# pCog102_Wifi_PSPJoy_BLED_TFT.net
KiCad netlist of a schematic drawn in EAGLE
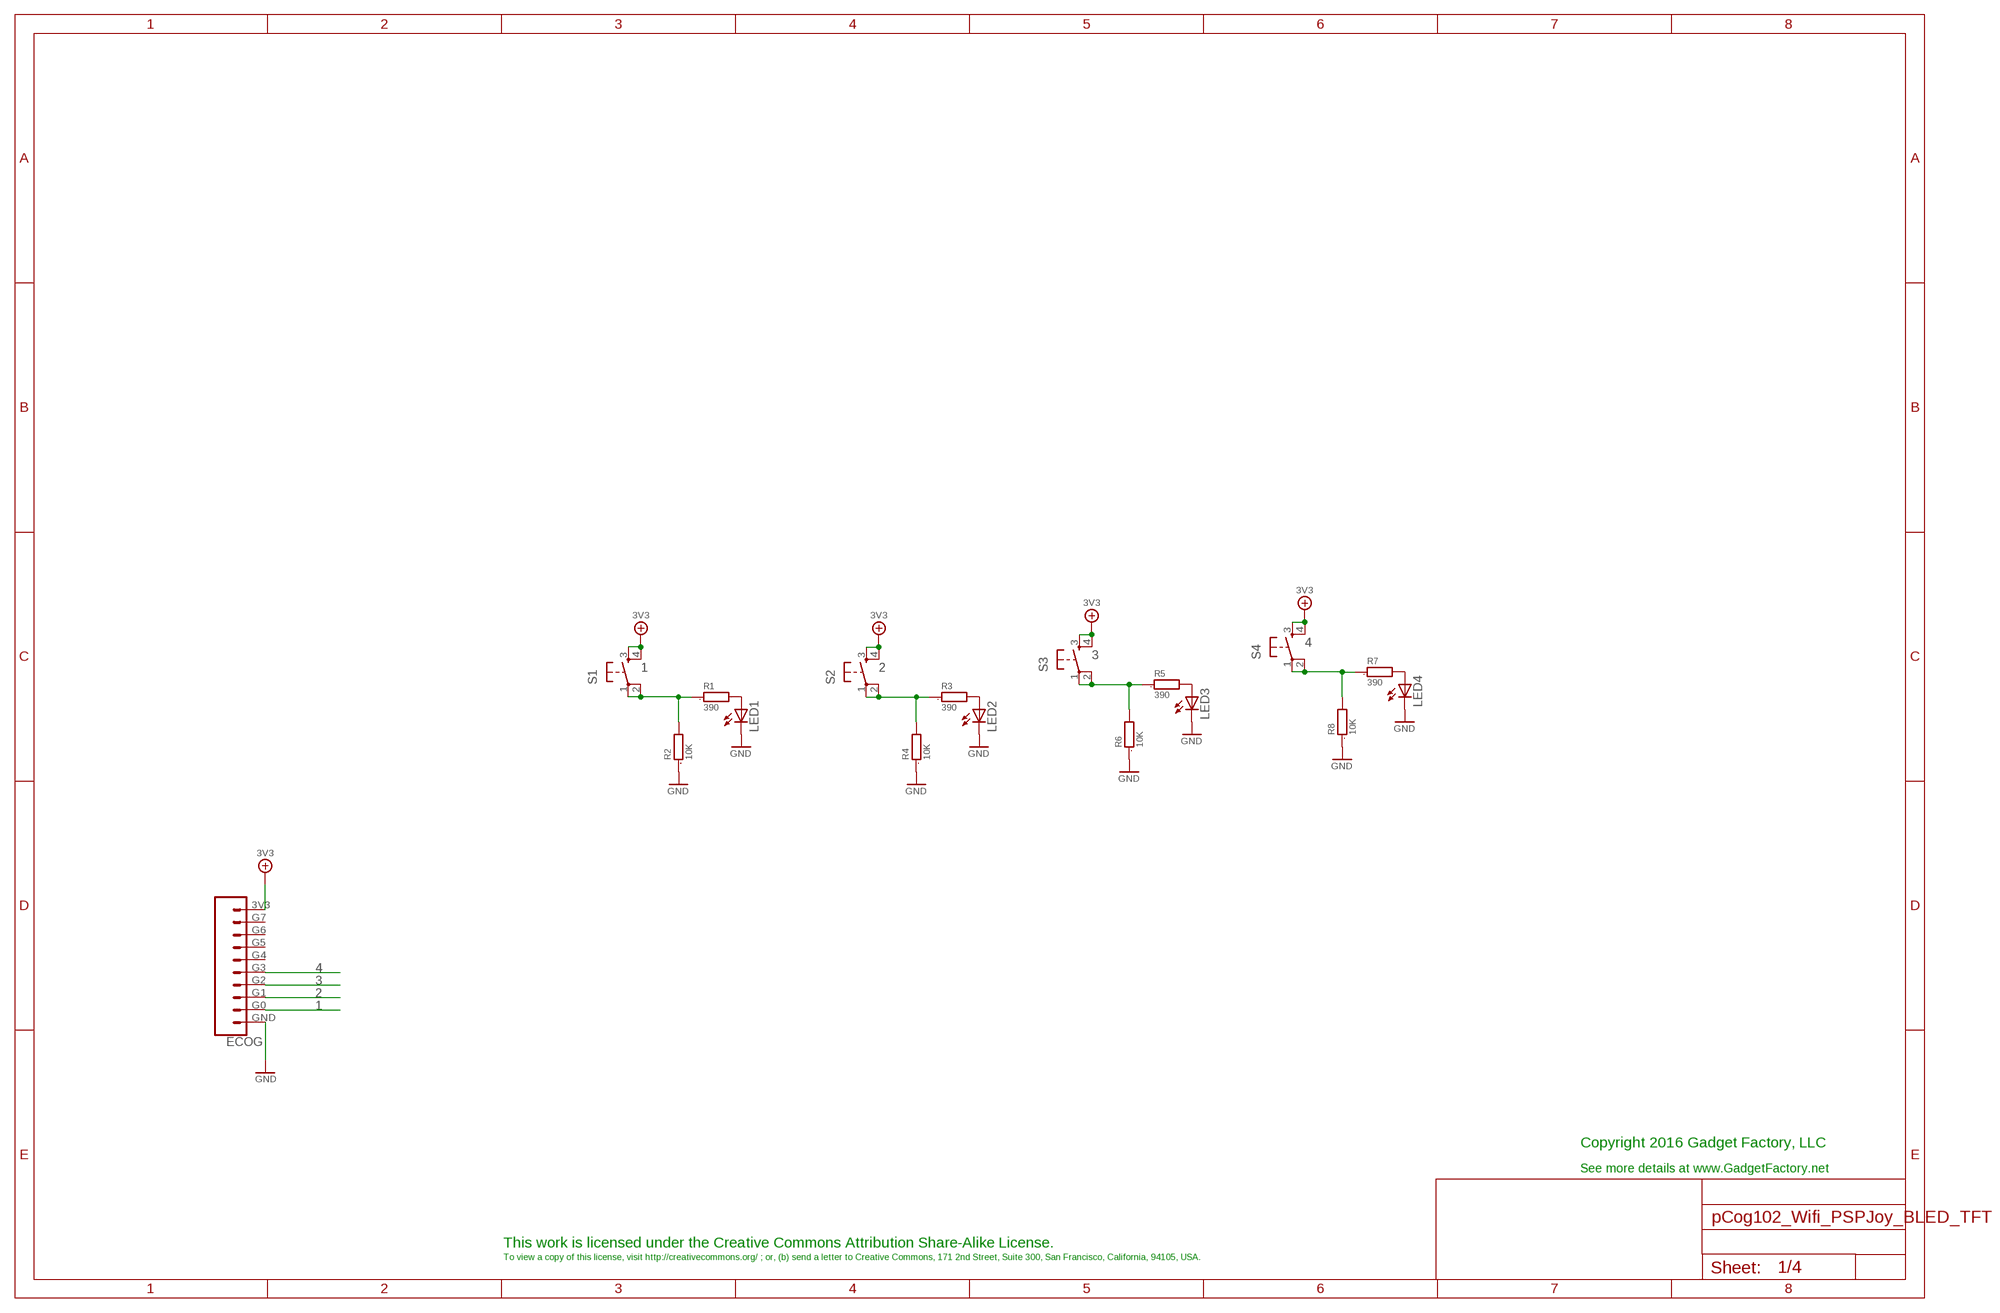
[diagram p0: schematic, sheet 1]
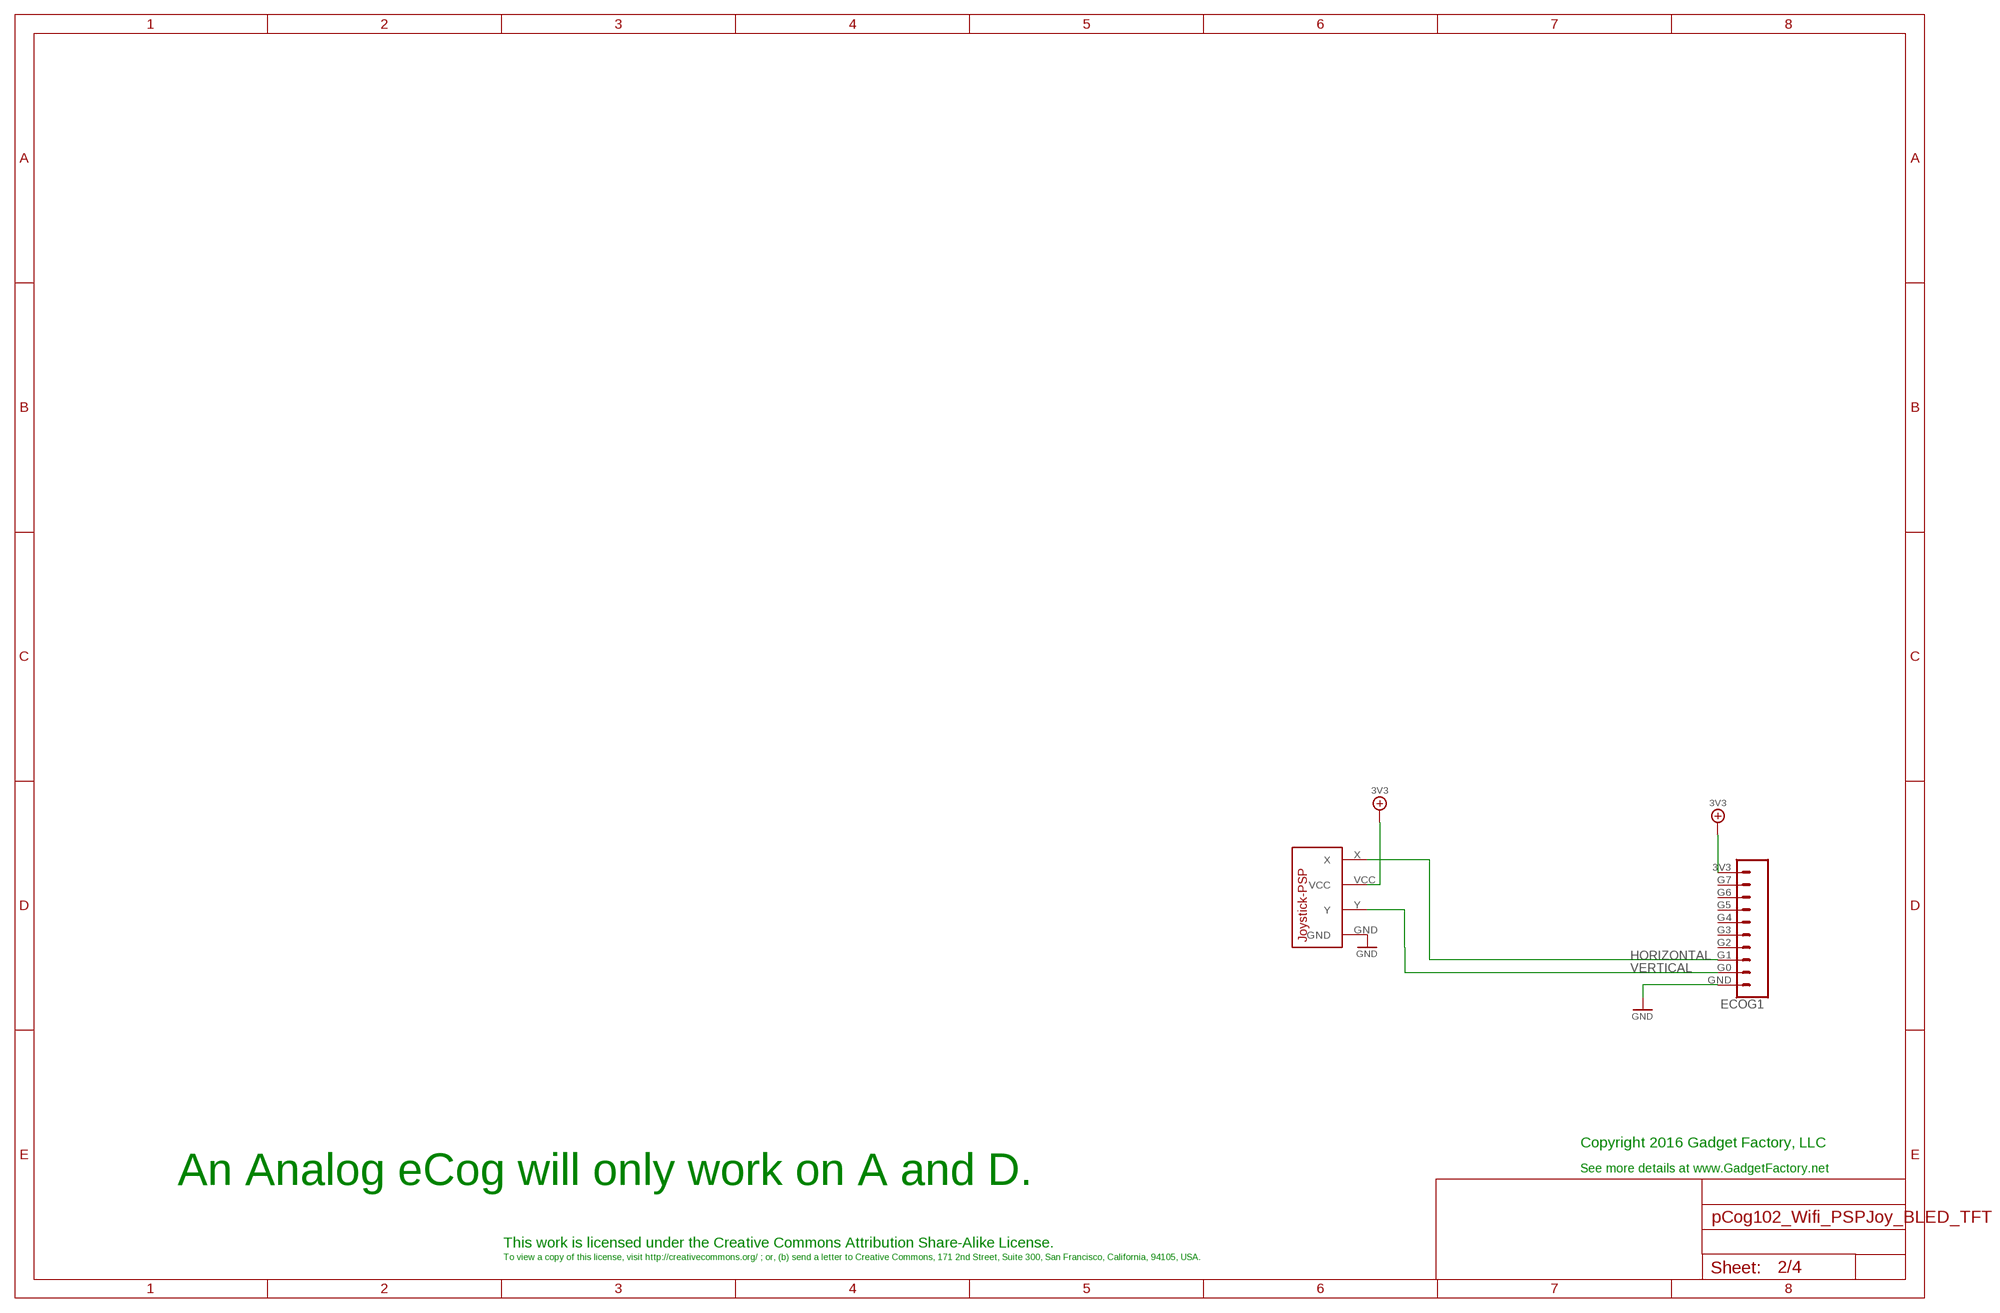
[diagram p1: schematic, sheet 2]
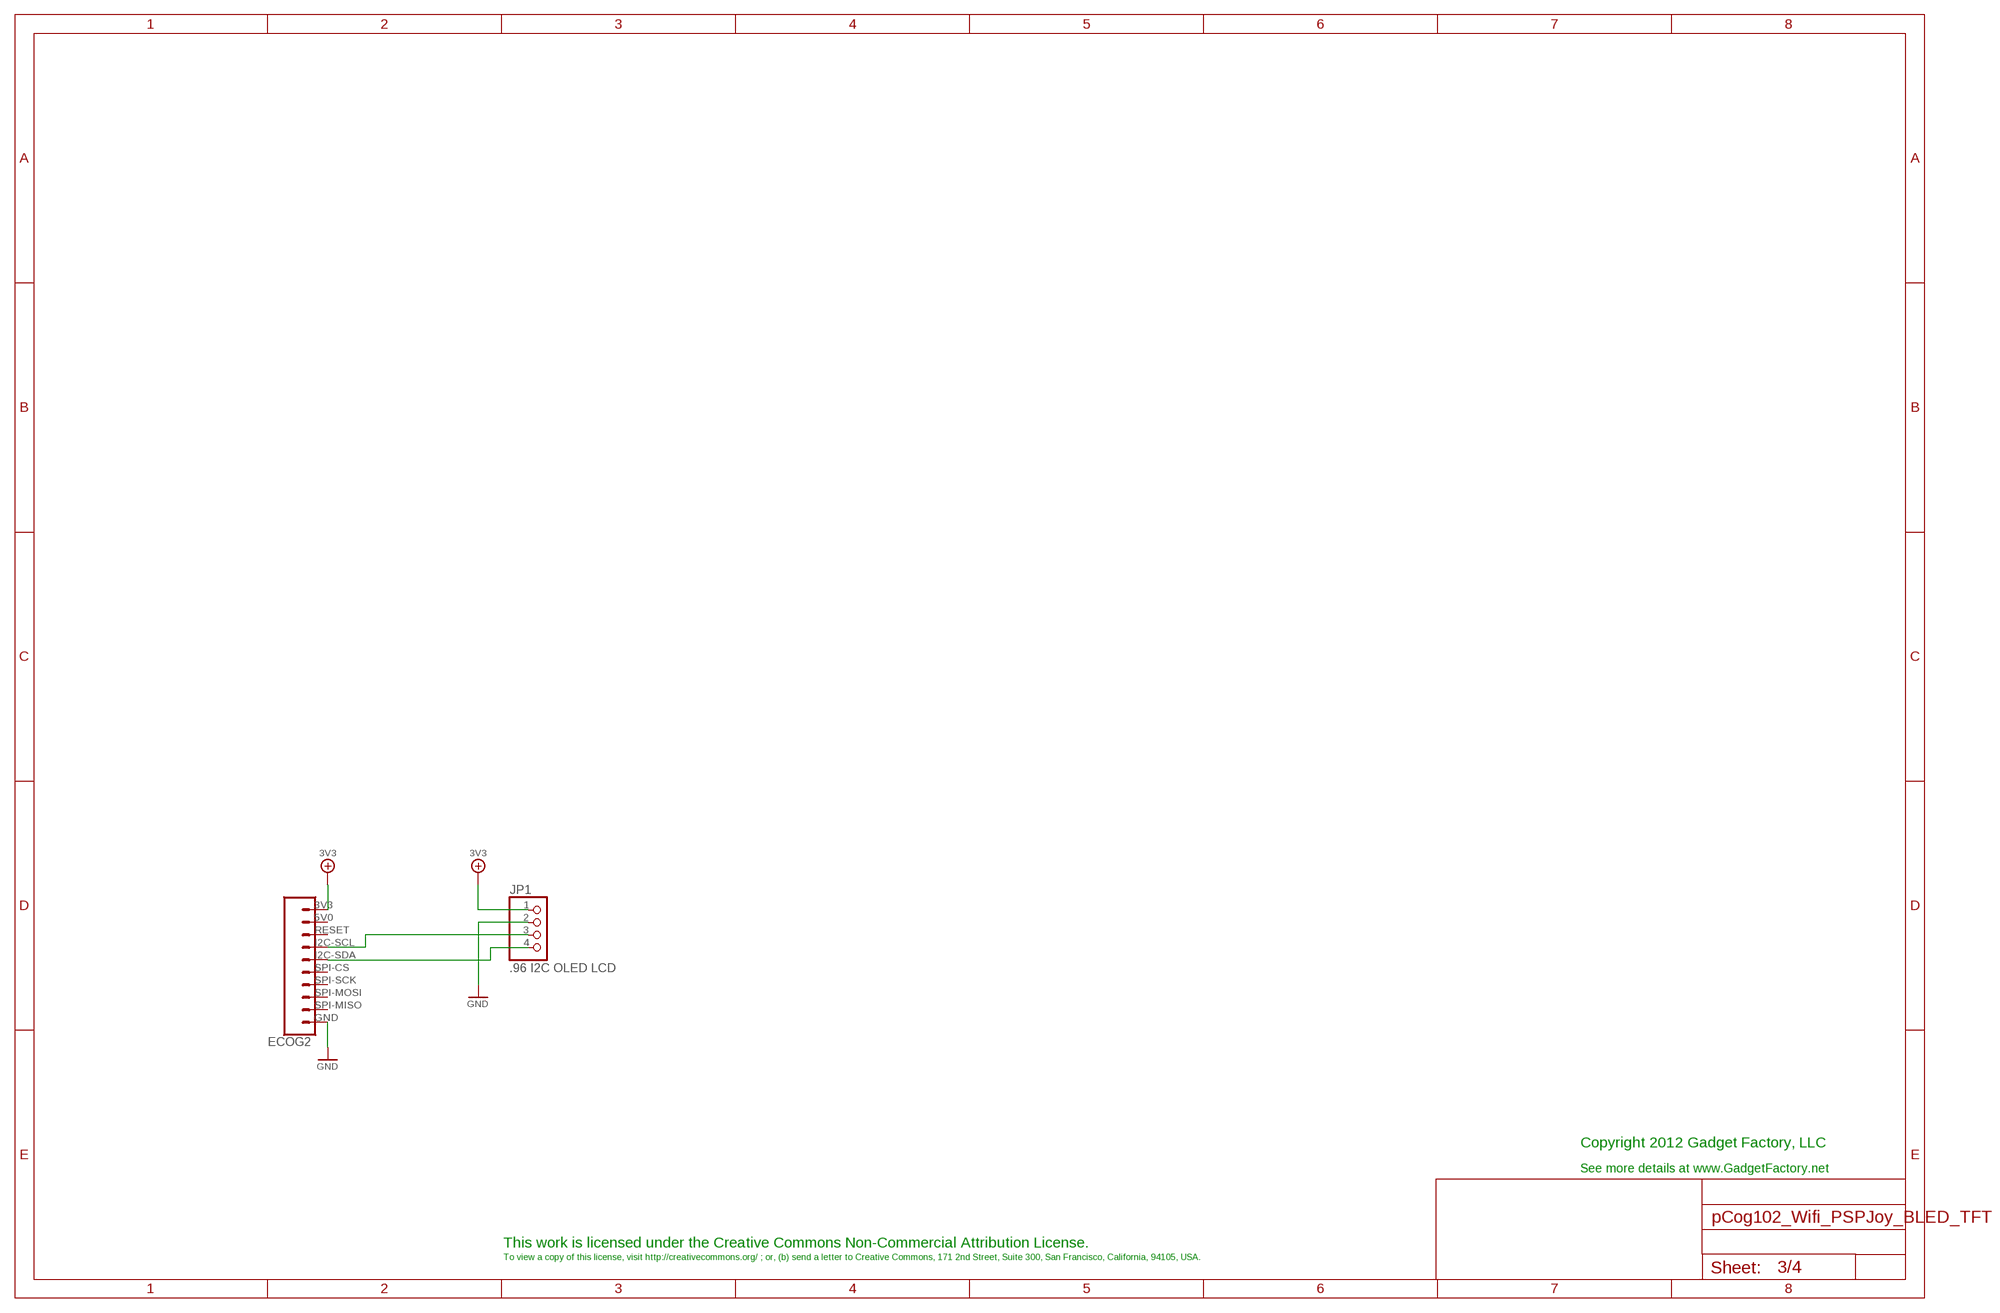
[diagram p2: schematic, sheet 3]
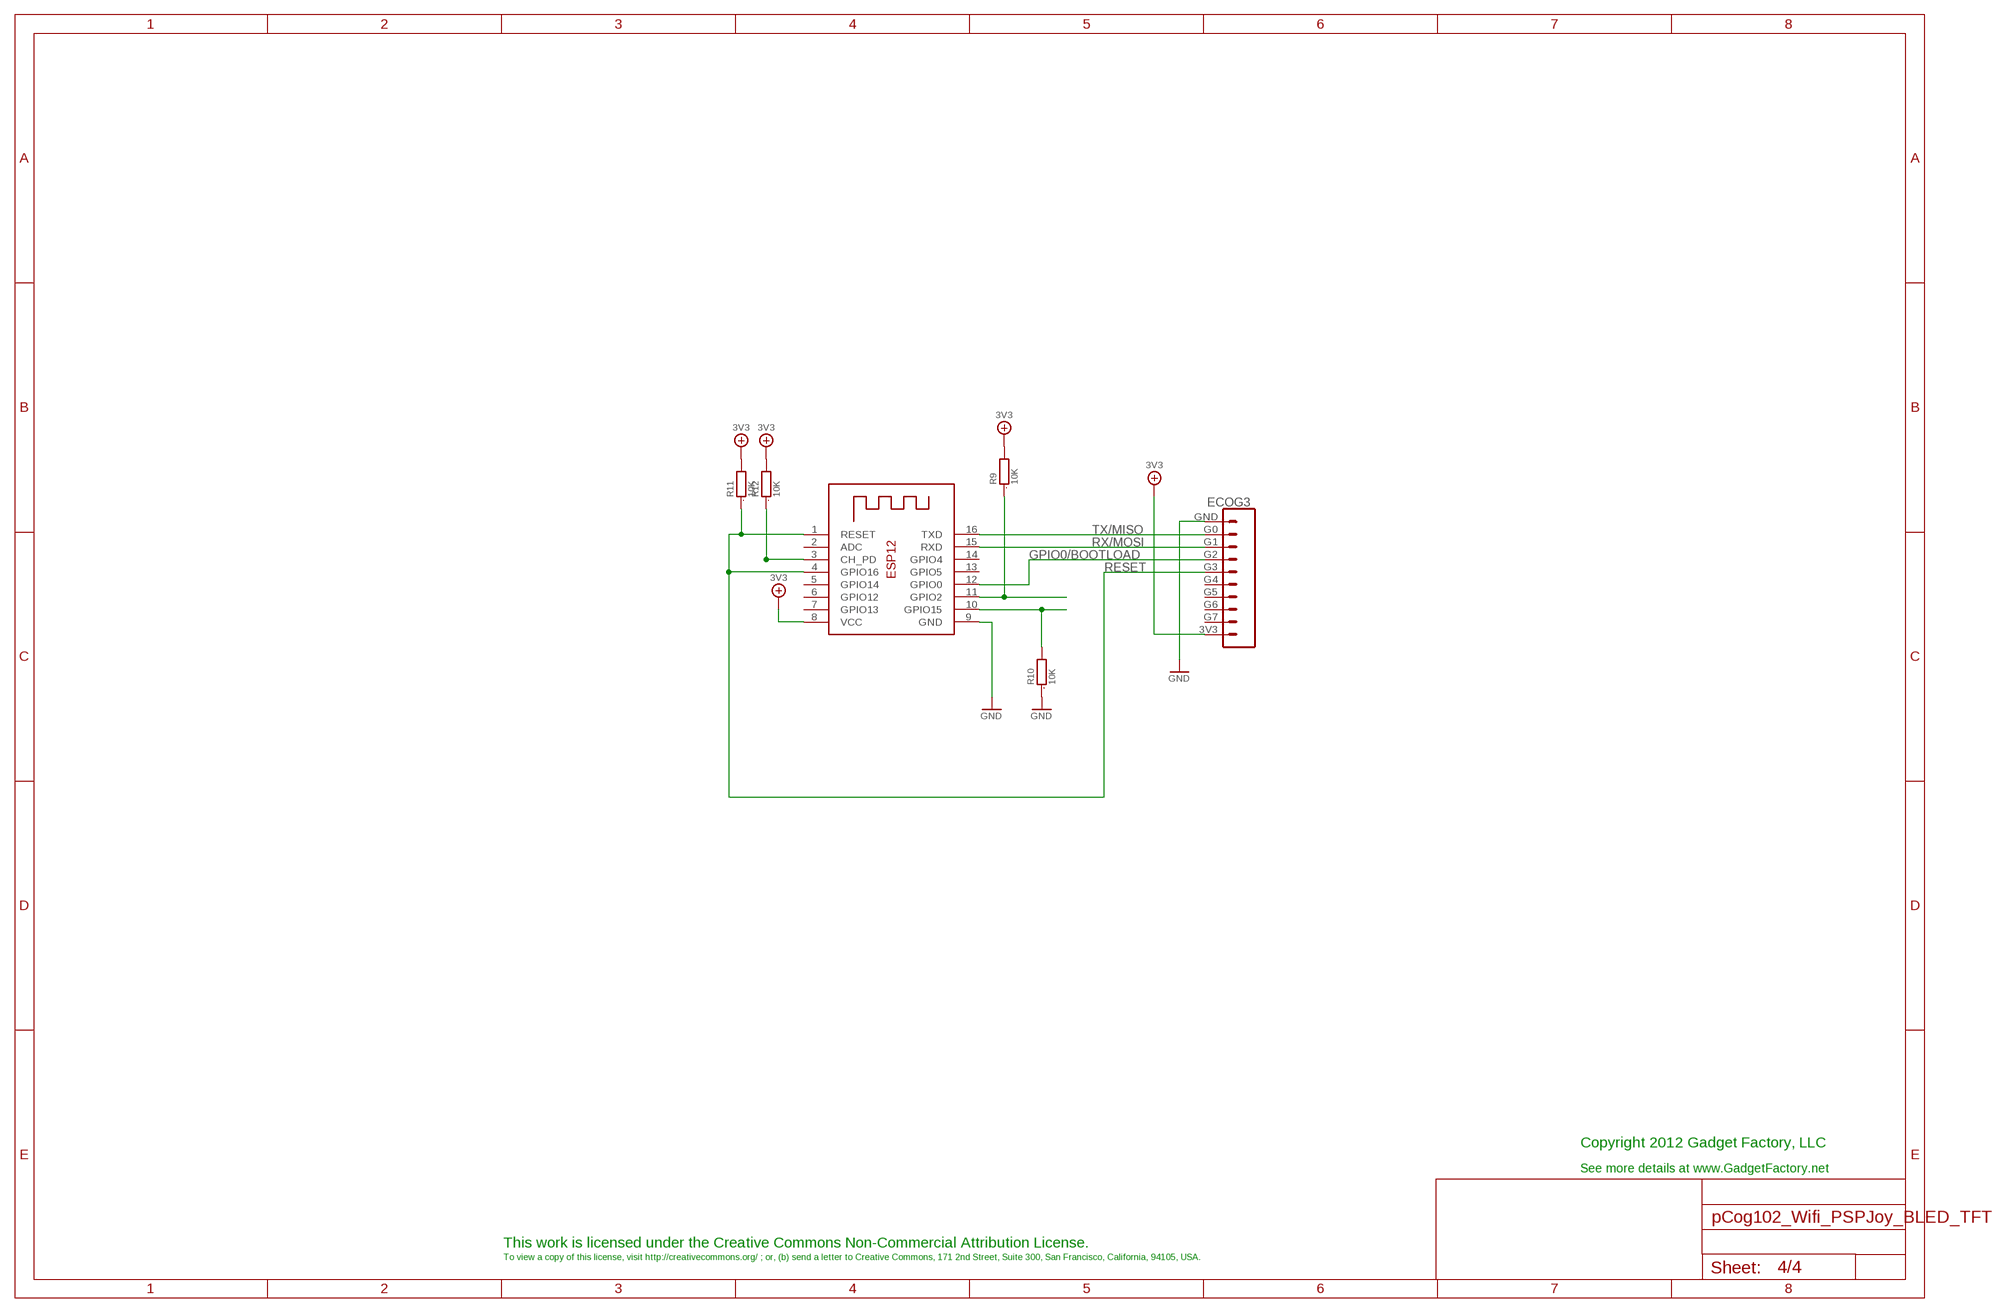
[diagram p3: schematic, sheet 4]

(export (version "E")
  (design (tool "Eeschema 10.0.6"))
  (components
    (comp (ref "ECOG")
      (value "ECOG_GENERAL_ROWECOG_GENERAL_SMD")
      (footprint "eagle-import:ECOG_GENERAL_SMD")
      (libsource (lib "eagle-import") (part "ECOG_GENERAL_ROWECOG_GENERAL_SMD"))
    )
    (comp (ref "LED1")
      (value "LEDCHIP-LED0805")
      (footprint "eagle-import:CHIP-LED0805")
      (libsource (lib "eagle-import") (part "LEDCHIP-LED0805"))
    )
    (comp (ref "LED2")
      (value "LEDCHIP-LED0805")
      (footprint "eagle-import:CHIP-LED0805")
      (libsource (lib "eagle-import") (part "LEDCHIP-LED0805"))
    )
    (comp (ref "LED3")
      (value "LEDCHIP-LED0805")
      (footprint "eagle-import:CHIP-LED0805")
      (libsource (lib "eagle-import") (part "LEDCHIP-LED0805"))
    )
    (comp (ref "LED4")
      (value "LEDCHIP-LED0805")
      (footprint "eagle-import:CHIP-LED0805")
      (libsource (lib "eagle-import") (part "LEDCHIP-LED0805"))
    )
    (comp (ref "R1")
      (value "390")
      (footprint "eagle-import:0805")
      (libsource (lib "eagle-import") (part "R0805"))
    )
    (comp (ref "R2")
      (value "10K")
      (footprint "eagle-import:0805")
      (libsource (lib "eagle-import") (part "R0805"))
    )
    (comp (ref "R3")
      (value "390")
      (footprint "eagle-import:0805")
      (libsource (lib "eagle-import") (part "R0805"))
    )
    (comp (ref "R4")
      (value "10K")
      (footprint "eagle-import:0805")
      (libsource (lib "eagle-import") (part "R0805"))
    )
    (comp (ref "R5")
      (value "390")
      (footprint "eagle-import:0805")
      (libsource (lib "eagle-import") (part "R0805"))
    )
    (comp (ref "R6")
      (value "10K")
      (footprint "eagle-import:0805")
      (libsource (lib "eagle-import") (part "R0805"))
    )
    (comp (ref "R7")
      (value "390")
      (footprint "eagle-import:0805")
      (libsource (lib "eagle-import") (part "R0805"))
    )
    (comp (ref "R8")
      (value "10K")
      (footprint "eagle-import:0805")
      (libsource (lib "eagle-import") (part "R0805"))
    )
    (comp (ref "S1")
      (value "TAC_SWITCHPTH")
      (footprint "eagle-import:TACTILE-PTH")
      (libsource (lib "eagle-import") (part "TAC_SWITCHPTH"))
    )
    (comp (ref "S2")
      (value "TAC_SWITCHPTH")
      (footprint "eagle-import:TACTILE-PTH")
      (libsource (lib "eagle-import") (part "TAC_SWITCHPTH"))
    )
    (comp (ref "S3")
      (value "TAC_SWITCHPTH")
      (footprint "eagle-import:TACTILE-PTH")
      (libsource (lib "eagle-import") (part "TAC_SWITCHPTH"))
    )
    (comp (ref "S4")
      (value "TAC_SWITCHPTH")
      (footprint "eagle-import:TACTILE-PTH")
      (libsource (lib "eagle-import") (part "TAC_SWITCHPTH"))
    )
    (comp (ref "ECOG2")
      (value "ECOG_BUSES_ROWECOG_BUSES_SMD")
      (footprint "eagle-import:ECOG_BUSES_SMD")
      (libsource (lib "eagle-import") (part "ECOG_BUSES_ROWECOG_BUSES_SMD"))
    )
    (comp (ref "JP1")
      (value ".96 I2C OLED LCD")
      (footprint "eagle-import:1X04")
      (libsource (lib "eagle-import") (part "PINHD-1X4"))
    )
    (comp (ref "ECOG3")
      (value "ECOG_GENERAL_ROWECOG_GENERAL_SMD")
      (footprint "eagle-import:ECOG_GENERAL_SMD")
      (libsource (lib "eagle-import") (part "ECOG_GENERAL_ROWECOG_GENERAL_SMD"))
    )
    (comp (ref "R9")
      (value "10K")
      (footprint "eagle-import:0805")
      (libsource (lib "eagle-import") (part "R0805"))
    )
    (comp (ref "R10")
      (value "10K")
      (footprint "eagle-import:0805")
      (libsource (lib "eagle-import") (part "R0805"))
    )
    (comp (ref "R11")
      (value "10K")
      (footprint "eagle-import:0805")
      (libsource (lib "eagle-import") (part "R0805"))
    )
    (comp (ref "R12")
      (value "10K")
      (footprint "eagle-import:0805")
      (libsource (lib "eagle-import") (part "R0805"))
    )
    (comp (ref "X1")
      (value "ESP-12")
      (footprint "eagle-import:ESP-12")
      (libsource (lib "eagle-import") (part "ESP-12"))
    )
    (comp (ref "ECOG1")
      (value "ECOG_GENERAL_ROWECOG_GENERAL_SMD")
      (footprint "eagle-import:ECOG_GENERAL_SMD")
      (libsource (lib "eagle-import") (part "ECOG_GENERAL_ROWECOG_GENERAL_SMD"))
    )
    (comp (ref "U$7")
      (value "JOYSTICK-PSP1000")
      (footprint "eagle-import:JOYSTICK-PSP1000")
      (libsource (lib "eagle-import") (part "JOYSTICK-PSP1000"))
    )
  )
  (nets
    (net (code "1") (name "1") (class "Default")
      (node (ref "ECOG") (pin "G0") (pinfunction "G0_G0") (pintype "passive"))
      (node (ref "R1") (pin "1") (pinfunction "1_1") (pintype "passive"))
      (node (ref "R2") (pin "2") (pinfunction "2_2") (pintype "passive"))
      (node (ref "S1") (pin "1") (pinfunction "1_1") (pintype "passive"))
      (node (ref "S1") (pin "2") (pinfunction "2_2") (pintype "passive"))
    )
    (net (code "2") (name "2") (class "Default")
      (node (ref "ECOG") (pin "G1") (pinfunction "G1_G1") (pintype "passive"))
      (node (ref "R3") (pin "1") (pinfunction "1_1") (pintype "passive"))
      (node (ref "R4") (pin "2") (pinfunction "2_2") (pintype "passive"))
      (node (ref "S2") (pin "1") (pinfunction "1_1") (pintype "passive"))
      (node (ref "S2") (pin "2") (pinfunction "2_2") (pintype "passive"))
    )
    (net (code "3") (name "3") (class "Default")
      (node (ref "ECOG") (pin "G2") (pinfunction "G2_G2") (pintype "passive"))
      (node (ref "R5") (pin "1") (pinfunction "1_1") (pintype "passive"))
      (node (ref "R6") (pin "2") (pinfunction "2_2") (pintype "passive"))
      (node (ref "S3") (pin "1") (pinfunction "1_1") (pintype "passive"))
      (node (ref "S3") (pin "2") (pinfunction "2_2") (pintype "passive"))
    )
    (net (code "4") (name "3V3") (class "Default")
      (node (ref "ECOG") (pin "3V3") (pinfunction "3V3_3V3") (pintype "power_in"))
      (node (ref "ECOG1") (pin "3V3") (pinfunction "3V3_3V3") (pintype "power_in"))
      (node (ref "ECOG2") (pin "3V3") (pinfunction "3V3_3V3") (pintype "passive"))
      (node (ref "ECOG3") (pin "3V3") (pinfunction "3V3_3V3") (pintype "power_in"))
      (node (ref "JP1") (pin "1") (pinfunction "1_1") (pintype "passive"))
      (node (ref "R11") (pin "2") (pinfunction "2_2") (pintype "passive"))
      (node (ref "R12") (pin "2") (pinfunction "2_2") (pintype "passive"))
      (node (ref "R9") (pin "2") (pinfunction "2_2") (pintype "passive"))
      (node (ref "S1") (pin "3") (pinfunction "3_3") (pintype "passive"))
      (node (ref "S1") (pin "4") (pinfunction "4_4") (pintype "passive"))
      (node (ref "S2") (pin "3") (pinfunction "3_3") (pintype "passive"))
      (node (ref "S2") (pin "4") (pinfunction "4_4") (pintype "passive"))
      (node (ref "S3") (pin "3") (pinfunction "3_3") (pintype "passive"))
      (node (ref "S3") (pin "4") (pinfunction "4_4") (pintype "passive"))
      (node (ref "S4") (pin "3") (pinfunction "3_3") (pintype "passive"))
      (node (ref "S4") (pin "4") (pinfunction "4_4") (pintype "passive"))
      (node (ref "U$7") (pin "VCC") (pinfunction "VCC_VCC") (pintype "bidirectional"))
      (node (ref "X1") (pin "8") (pinfunction "VCC_8") (pintype "power_in"))
    )
    (net (code "5") (name "4") (class "Default")
      (node (ref "ECOG") (pin "G3") (pinfunction "G3_G3") (pintype "passive"))
      (node (ref "R7") (pin "1") (pinfunction "1_1") (pintype "passive"))
      (node (ref "R8") (pin "2") (pinfunction "2_2") (pintype "passive"))
      (node (ref "S4") (pin "1") (pinfunction "1_1") (pintype "passive"))
      (node (ref "S4") (pin "2") (pinfunction "2_2") (pintype "passive"))
    )
    (net (code "6") (name "GND") (class "Default")
      (node (ref "ECOG") (pin "GND") (pinfunction "GND_GND") (pintype "power_in"))
      (node (ref "ECOG1") (pin "GND") (pinfunction "GND_GND") (pintype "power_in"))
      (node (ref "ECOG2") (pin "GND") (pinfunction "GND_GND") (pintype "passive"))
      (node (ref "ECOG3") (pin "GND") (pinfunction "GND_GND") (pintype "power_in"))
      (node (ref "JP1") (pin "2") (pinfunction "2_2") (pintype "passive"))
      (node (ref "LED1") (pin "C") (pinfunction "C_C") (pintype "passive"))
      (node (ref "LED2") (pin "C") (pinfunction "C_C") (pintype "passive"))
      (node (ref "LED3") (pin "C") (pinfunction "C_C") (pintype "passive"))
      (node (ref "LED4") (pin "C") (pinfunction "C_C") (pintype "passive"))
      (node (ref "R10") (pin "1") (pinfunction "1_1") (pintype "passive"))
      (node (ref "R2") (pin "1") (pinfunction "1_1") (pintype "passive"))
      (node (ref "R4") (pin "1") (pinfunction "1_1") (pintype "passive"))
      (node (ref "R6") (pin "1") (pinfunction "1_1") (pintype "passive"))
      (node (ref "R8") (pin "1") (pinfunction "1_1") (pintype "passive"))
      (node (ref "U$7") (pin "GND") (pinfunction "GND_GND") (pintype "bidirectional"))
      (node (ref "X1") (pin "9") (pinfunction "GND_9") (pintype "power_in"))
    )
    (net (code "7") (name "GPIO0{slash}BOOTLOAD") (class "Default")
      (node (ref "ECOG3") (pin "G2") (pinfunction "G2_G2") (pintype "passive"))
      (node (ref "X1") (pin "12") (pinfunction "GPIO0_12") (pintype "bidirectional"))
    )
    (net (code "8") (name "HORIZONTAL") (class "Default")
      (node (ref "ECOG1") (pin "G1") (pinfunction "G1_G1") (pintype "passive"))
      (node (ref "U$7") (pin "X") (pinfunction "X_X") (pintype "bidirectional"))
    )
    (net (code "9") (name "Net-(ECOG2-PadI2C-SCL)") (class "Default")
      (node (ref "ECOG2") (pin "I2C-SCL") (pinfunction "I2C-SCL_I2C-SCL") (pintype "passive"))
      (node (ref "JP1") (pin "3") (pinfunction "3_3") (pintype "passive"))
    )
    (net (code "10") (name "Net-(ECOG2-PadI2C-SDA)") (class "Default")
      (node (ref "ECOG2") (pin "I2C-SDA") (pinfunction "I2C-SDA_I2C-SDA") (pintype "passive"))
      (node (ref "JP1") (pin "4") (pinfunction "4_4") (pintype "passive"))
    )
    (net (code "11") (name "Net-(LED1-PadA)") (class "Default")
      (node (ref "LED1") (pin "A") (pinfunction "A_A") (pintype "passive"))
      (node (ref "R1") (pin "2") (pinfunction "2_2") (pintype "passive"))
    )
    (net (code "12") (name "Net-(LED2-PadA)") (class "Default")
      (node (ref "LED2") (pin "A") (pinfunction "A_A") (pintype "passive"))
      (node (ref "R3") (pin "2") (pinfunction "2_2") (pintype "passive"))
    )
    (net (code "13") (name "Net-(LED3-PadA)") (class "Default")
      (node (ref "LED3") (pin "A") (pinfunction "A_A") (pintype "passive"))
      (node (ref "R5") (pin "2") (pinfunction "2_2") (pintype "passive"))
    )
    (net (code "14") (name "Net-(LED4-PadA)") (class "Default")
      (node (ref "LED4") (pin "A") (pinfunction "A_A") (pintype "passive"))
      (node (ref "R7") (pin "2") (pinfunction "2_2") (pintype "passive"))
    )
    (net (code "15") (name "Net-(X1-CH_PD)") (class "Default")
      (node (ref "R12") (pin "1") (pinfunction "1_1") (pintype "passive"))
      (node (ref "X1") (pin "3") (pinfunction "CH_PD_3") (pintype "input"))
    )
    (net (code "16") (name "Net-(X1-GPIO2)") (class "Default")
      (node (ref "R9") (pin "1") (pinfunction "1_1") (pintype "passive"))
      (node (ref "X1") (pin "11") (pinfunction "GPIO2_11") (pintype "bidirectional"))
    )
    (net (code "17") (name "Net-(X1-GPIO15)") (class "Default")
      (node (ref "R10") (pin "2") (pinfunction "2_2") (pintype "passive"))
      (node (ref "X1") (pin "10") (pinfunction "GPIO15_10") (pintype "bidirectional"))
    )
    (net (code "18") (name "RESET") (class "Default")
      (node (ref "ECOG3") (pin "G3") (pinfunction "G3_G3") (pintype "passive"))
      (node (ref "R11") (pin "1") (pinfunction "1_1") (pintype "passive"))
      (node (ref "X1") (pin "1") (pinfunction "RESET_1") (pintype "input"))
      (node (ref "X1") (pin "4") (pinfunction "GPIO16_4") (pintype "bidirectional"))
    )
    (net (code "19") (name "RX{slash}MOSI") (class "Default")
      (node (ref "ECOG3") (pin "G1") (pinfunction "G1_G1") (pintype "passive"))
      (node (ref "X1") (pin "15") (pinfunction "RXD_15") (pintype "input"))
    )
    (net (code "20") (name "TX{slash}MISO") (class "Default")
      (node (ref "ECOG3") (pin "G0") (pinfunction "G0_G0") (pintype "passive"))
      (node (ref "X1") (pin "16") (pinfunction "TXD_16") (pintype "output"))
    )
    (net (code "21") (name "VERTICAL") (class "Default")
      (node (ref "ECOG1") (pin "G0") (pinfunction "G0_G0") (pintype "passive"))
      (node (ref "U$7") (pin "Y") (pinfunction "Y_Y") (pintype "bidirectional"))
    )
    (net (code "22") (name "unconnected-(ECOG-PadG4)") (class "Default")
      (node (ref "ECOG") (pin "G4") (pinfunction "G4_G4") (pintype "passive"))
    )
    (net (code "23") (name "unconnected-(ECOG-PadG5)") (class "Default")
      (node (ref "ECOG") (pin "G5") (pinfunction "G5_G5") (pintype "passive"))
    )
    (net (code "24") (name "unconnected-(ECOG-PadG6)") (class "Default")
      (node (ref "ECOG") (pin "G6") (pinfunction "G6_G6") (pintype "passive"))
    )
    (net (code "25") (name "unconnected-(ECOG-PadG7)") (class "Default")
      (node (ref "ECOG") (pin "G7") (pinfunction "G7_G7") (pintype "passive"))
    )
    (net (code "26") (name "unconnected-(ECOG1-PadG2)") (class "Default")
      (node (ref "ECOG1") (pin "G2") (pinfunction "G2_G2") (pintype "passive"))
    )
    (net (code "27") (name "unconnected-(ECOG1-PadG3)") (class "Default")
      (node (ref "ECOG1") (pin "G3") (pinfunction "G3_G3") (pintype "passive"))
    )
    (net (code "28") (name "unconnected-(ECOG1-PadG4)") (class "Default")
      (node (ref "ECOG1") (pin "G4") (pinfunction "G4_G4") (pintype "passive"))
    )
    (net (code "29") (name "unconnected-(ECOG1-PadG5)") (class "Default")
      (node (ref "ECOG1") (pin "G5") (pinfunction "G5_G5") (pintype "passive"))
    )
    (net (code "30") (name "unconnected-(ECOG1-PadG6)") (class "Default")
      (node (ref "ECOG1") (pin "G6") (pinfunction "G6_G6") (pintype "passive"))
    )
    (net (code "31") (name "unconnected-(ECOG1-PadG7)") (class "Default")
      (node (ref "ECOG1") (pin "G7") (pinfunction "G7_G7") (pintype "passive"))
    )
    (net (code "32") (name "unconnected-(ECOG2-Pad5V0)") (class "Default")
      (node (ref "ECOG2") (pin "5V0") (pinfunction "5V0_5V0") (pintype "passive"))
    )
    (net (code "33") (name "unconnected-(ECOG2-PadRESET)") (class "Default")
      (node (ref "ECOG2") (pin "RESET") (pinfunction "RESET_RESET") (pintype "passive"))
    )
    (net (code "34") (name "unconnected-(ECOG2-PadSPI-CS)") (class "Default")
      (node (ref "ECOG2") (pin "SPI-CS") (pinfunction "SPI-CS_SPI-CS") (pintype "passive"))
    )
    (net (code "35") (name "unconnected-(ECOG2-PadSPI-MISO)") (class "Default")
      (node (ref "ECOG2") (pin "SPI-MISO") (pinfunction "SPI-MISO_SPI-MISO") (pintype "passive"))
    )
    (net (code "36") (name "unconnected-(ECOG2-PadSPI-MOSI)") (class "Default")
      (node (ref "ECOG2") (pin "SPI-MOSI") (pinfunction "SPI-MOSI_SPI-MOSI") (pintype "passive"))
    )
    (net (code "37") (name "unconnected-(ECOG2-PadSPI-SCK)") (class "Default")
      (node (ref "ECOG2") (pin "SPI-SCK") (pinfunction "SPI-SCK_SPI-SCK") (pintype "passive"))
    )
    (net (code "38") (name "unconnected-(ECOG3-PadG4)") (class "Default")
      (node (ref "ECOG3") (pin "G4") (pinfunction "G4_G4") (pintype "passive"))
    )
    (net (code "39") (name "unconnected-(ECOG3-PadG5)") (class "Default")
      (node (ref "ECOG3") (pin "G5") (pinfunction "G5_G5") (pintype "passive"))
    )
    (net (code "40") (name "unconnected-(ECOG3-PadG6)") (class "Default")
      (node (ref "ECOG3") (pin "G6") (pinfunction "G6_G6") (pintype "passive"))
    )
    (net (code "41") (name "unconnected-(ECOG3-PadG7)") (class "Default")
      (node (ref "ECOG3") (pin "G7") (pinfunction "G7_G7") (pintype "passive"))
    )
    (net (code "42") (name "unconnected-(X1-ADC-Pad2)") (class "Default")
      (node (ref "X1") (pin "2") (pinfunction "ADC_2") (pintype "passive"))
    )
    (net (code "43") (name "unconnected-(X1-GPIO4-Pad14)") (class "Default")
      (node (ref "X1") (pin "14") (pinfunction "GPIO4_14") (pintype "bidirectional"))
    )
    (net (code "44") (name "unconnected-(X1-GPIO5-Pad13)") (class "Default")
      (node (ref "X1") (pin "13") (pinfunction "GPIO5_13") (pintype "bidirectional"))
    )
    (net (code "45") (name "unconnected-(X1-GPIO12-Pad6)") (class "Default")
      (node (ref "X1") (pin "6") (pinfunction "GPIO12_6") (pintype "bidirectional"))
    )
    (net (code "46") (name "unconnected-(X1-GPIO13-Pad7)") (class "Default")
      (node (ref "X1") (pin "7") (pinfunction "GPIO13_7") (pintype "bidirectional"))
    )
    (net (code "47") (name "unconnected-(X1-GPIO14-Pad5)") (class "Default")
      (node (ref "X1") (pin "5") (pinfunction "GPIO14_5") (pintype "bidirectional"))
    )
  )
)
